# Main_4000_Model_REV1A.net
KiCad netlist of a schematic drawn in EAGLE
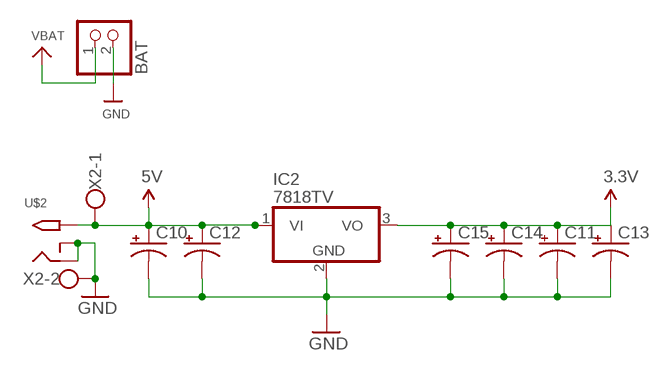
[diagram p0: schematic, sheet 1]
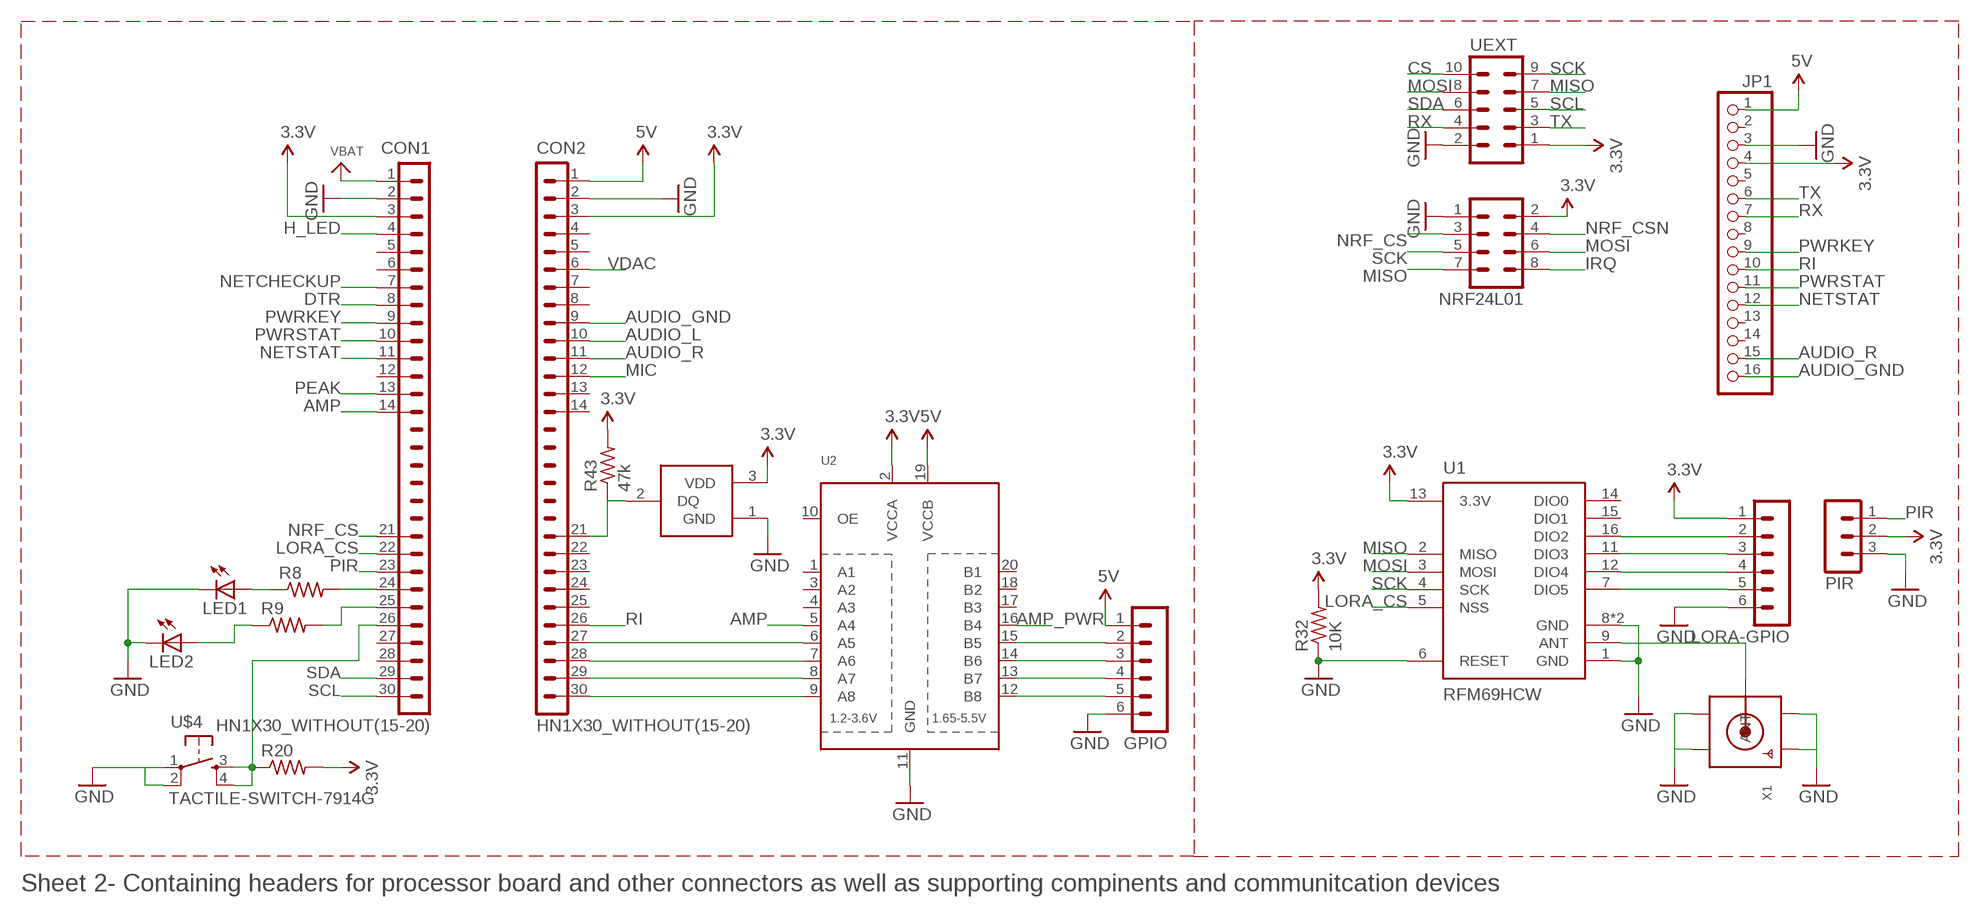
[diagram p1: schematic, sheet 2]
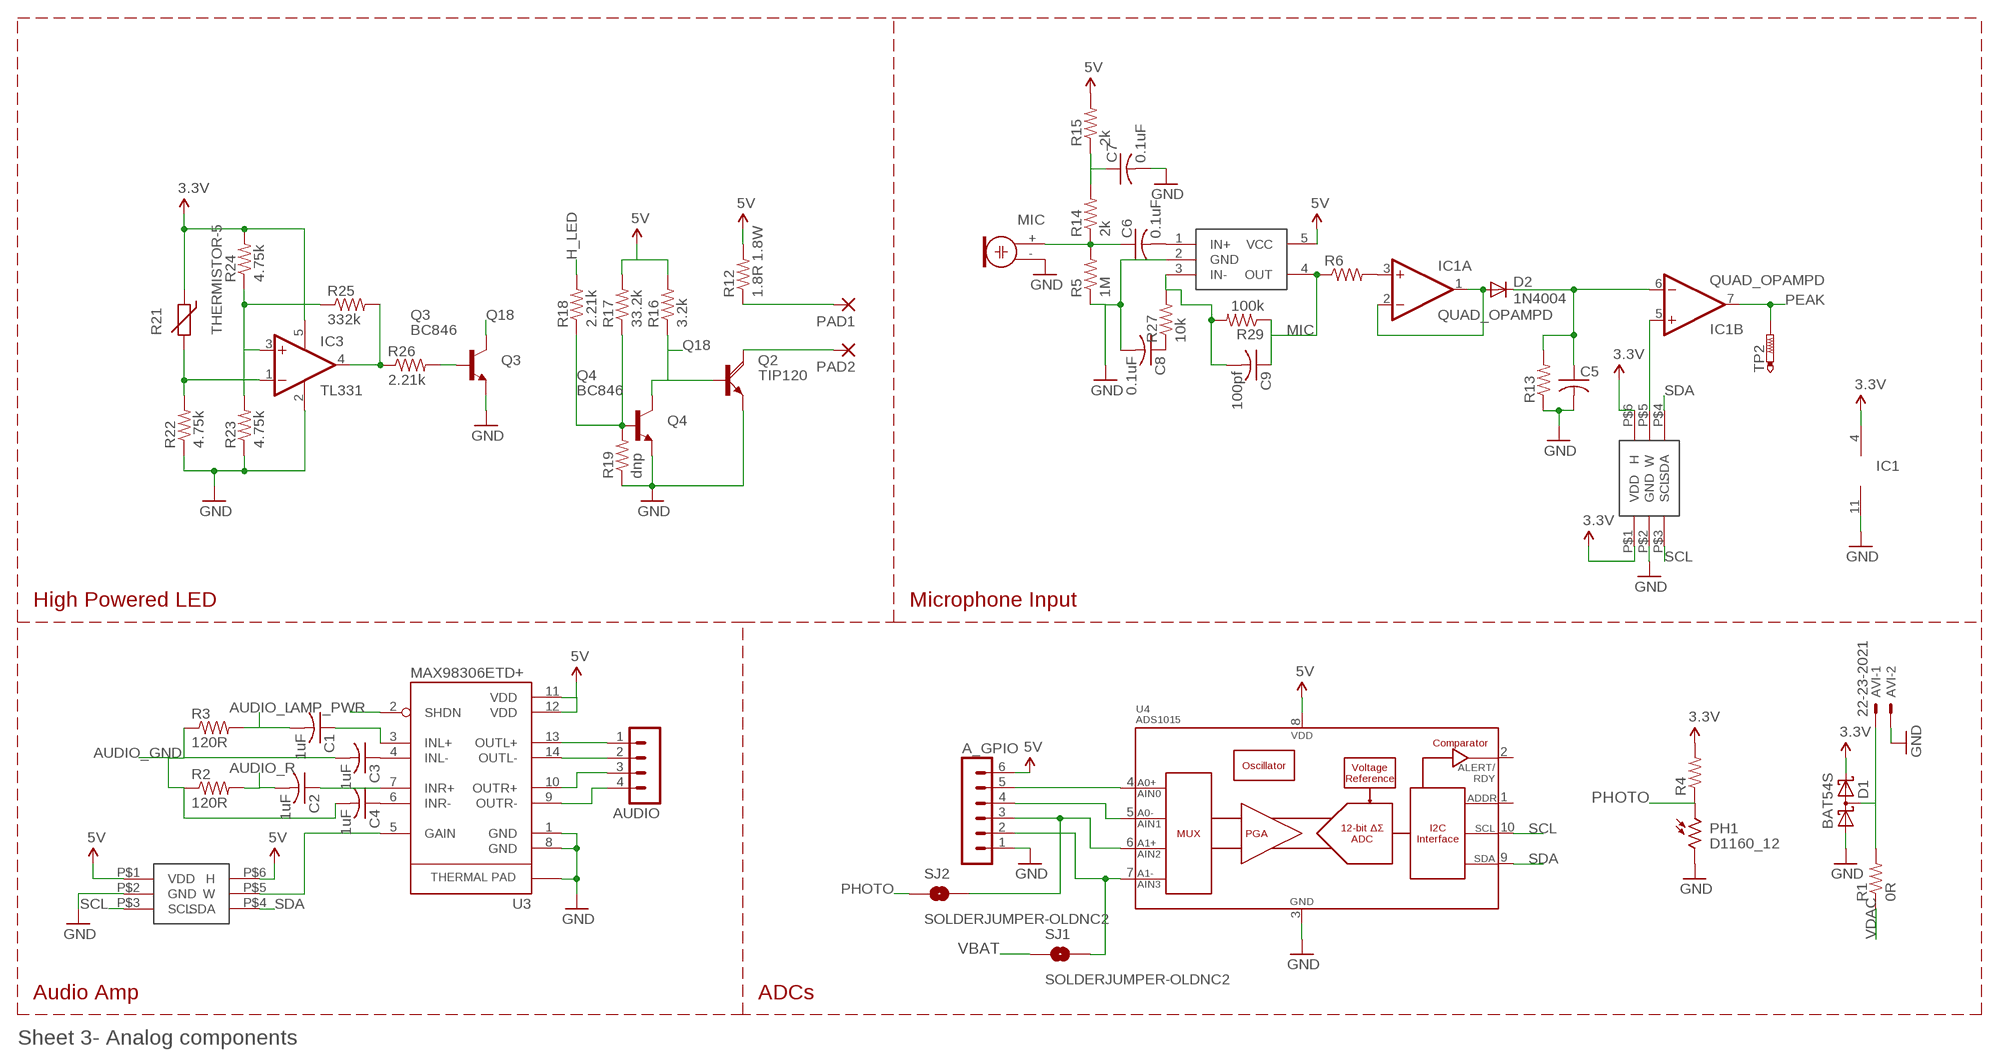
[diagram p2: schematic, sheet 3]
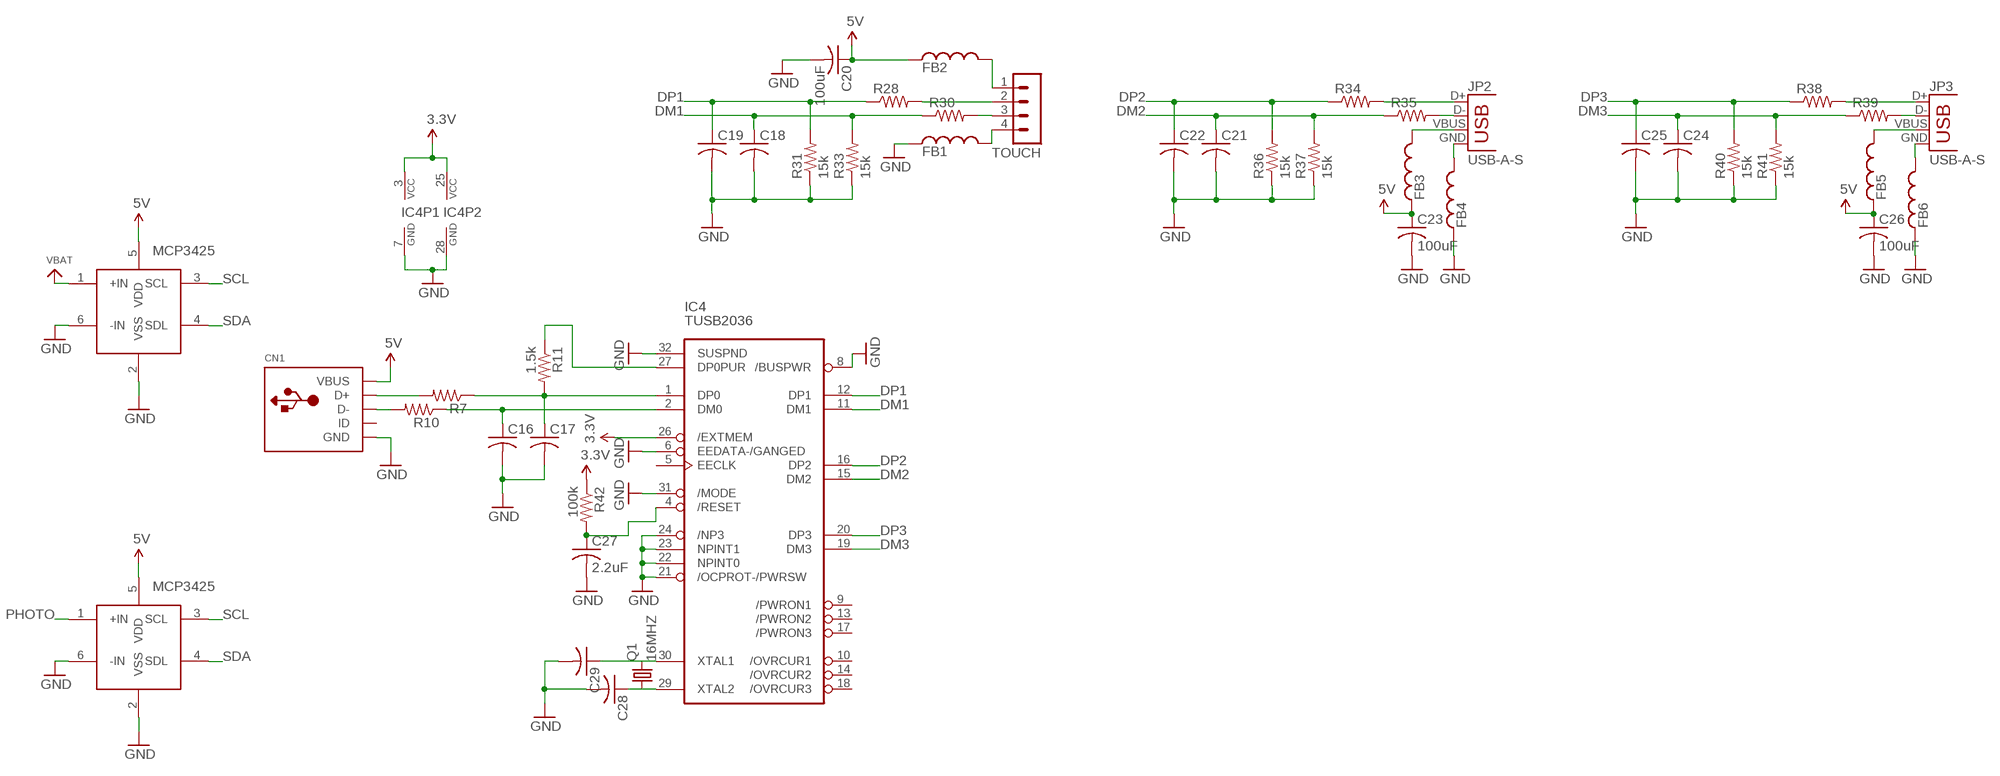
[diagram p3: schematic, sheet 4]

(export (version "E")
  (design (tool "Eeschema 10.0.6"))
  (components
    (comp (ref "CON1")
      (value "HN1X30_WITHOUT(15-20)")
      (footprint "eagle-import:HN1X30_WITHOUT(15-20)")
      (libsource (lib "eagle-import") (part "CON30_WITHOUT(15-20)"))
    )
    (comp (ref "CON2")
      (value "HN1X30_WITHOUT(15-20)")
      (footprint "eagle-import:HN1X30_WITHOUT(15-20)")
      (libsource (lib "eagle-import") (part "CON30_WITHOUT(15-20)"))
    )
    (comp (ref "GPIO")
      (value "MA06-1")
      (footprint "eagle-import:MA06-1")
      (libsource (lib "eagle-import") (part "MA06-1"))
    )
    (comp (ref "JP1")
      (value "PINHD-1X16")
      (footprint "eagle-import:1X16")
      (libsource (lib "eagle-import") (part "PINHD-1X16"))
    )
    (comp (ref "LED1")
      (value "LED5MM")
      (footprint "eagle-import:LED5MM")
      (libsource (lib "eagle-import") (part "LED5MM"))
    )
    (comp (ref "LED2")
      (value "LED5MM")
      (footprint "eagle-import:LED5MM")
      (libsource (lib "eagle-import") (part "LED5MM"))
    )
    (comp (ref "LORA-GPIO")
      (value "MA06-1")
      (footprint "eagle-import:MA06-1")
      (libsource (lib "eagle-import") (part "MA06-1"))
    )
    (comp (ref "NRF24L01")
      (value "MA04-2")
      (footprint "eagle-import:MA04-2")
      (libsource (lib "eagle-import") (part "MA04-2"))
    )
    (comp (ref "PIR")
      (value "MA03-1")
      (footprint "eagle-import:MA03-1")
      (libsource (lib "eagle-import") (part "MA03-1"))
    )
    (comp (ref "R8")
      (value "R-US_R0805")
      (footprint "eagle-import:R0805")
      (libsource (lib "eagle-import") (part "R-US_R0805"))
    )
    (comp (ref "R9")
      (value "R-US_R0805")
      (footprint "eagle-import:R0805")
      (libsource (lib "eagle-import") (part "R-US_R0805"))
    )
    (comp (ref "R20")
      (value "R-US_R0805")
      (footprint "eagle-import:R0805")
      (libsource (lib "eagle-import") (part "R-US_R0805"))
    )
    (comp (ref "R32")
      (value "10K")
      (footprint "eagle-import:R0805")
      (libsource (lib "eagle-import") (part "R-US_R0805"))
    )
    (comp (ref "R43")
      (value "47k")
      (footprint "eagle-import:R0805")
      (libsource (lib "eagle-import") (part "R-US_R0805"))
    )
    (comp (ref "U$4")
      (value "TACTILE-SWITCH-7914G")
      (footprint "eagle-import:7914G")
      (libsource (lib "eagle-import") (part "TACTILE-SWITCH-7914G"))
    )
    (comp (ref "U$11")
      (value "DS18B20Z")
      (footprint "eagle-import:TO92")
      (libsource (lib "eagle-import") (part "DS18B20Z"))
    )
    (comp (ref "U1")
      (value "RFM69HCW")
      (footprint "eagle-import:RFM69HCW-XXXS2")
      (libsource (lib "eagle-import") (part "RFM69HCW"))
    )
    (comp (ref "U2")
      (value "TXB0108PWR")
      (footprint "eagle-import:TSSOP20")
      (libsource (lib "eagle-import") (part "TXB0108PWR"))
    )
    (comp (ref "UEXT")
      (value "MA05-2")
      (footprint "eagle-import:MA05-2")
      (libsource (lib "eagle-import") (part "MA05-2"))
    )
    (comp (ref "X1")
      (value "SMACONNECTOR_EDGE")
      (footprint "eagle-import:SMA_EDGELAUNCH")
      (libsource (lib "eagle-import") (part "SMACONNECTOR_EDGE"))
    )
    (comp (ref "BAT")
      (value "JST_2PIN-SMT-RA")
      (footprint "eagle-import:JST-PH-2-SMT-RA")
      (libsource (lib "eagle-import") (part "JST_2PIN-SMT-RA"))
    )
    (comp (ref "C10")
      (value "CPOL-USE2.5-6")
      (footprint "eagle-import:E2,5-6")
      (libsource (lib "eagle-import") (part "CPOL-USE2.5-6"))
    )
    (comp (ref "C11")
      (value "CPOL-USE1.8-4")
      (footprint "eagle-import:E1,8-4")
      (libsource (lib "eagle-import") (part "CPOL-USE1.8-4"))
    )
    (comp (ref "C12")
      (value "CPOL-USE1.8-4")
      (footprint "eagle-import:E1,8-4")
      (libsource (lib "eagle-import") (part "CPOL-USE1.8-4"))
    )
    (comp (ref "C13")
      (value "CPOL-USE2.5-6")
      (footprint "eagle-import:E2,5-6")
      (libsource (lib "eagle-import") (part "CPOL-USE2.5-6"))
    )
    (comp (ref "C14")
      (value "CPOL-USE1.8-4")
      (footprint "eagle-import:E1,8-4")
      (libsource (lib "eagle-import") (part "CPOL-USE1.8-4"))
    )
    (comp (ref "C15")
      (value "CPOL-USE1.8-4")
      (footprint "eagle-import:E1,8-4")
      (libsource (lib "eagle-import") (part "CPOL-USE1.8-4"))
    )
    (comp (ref "IC2")
      (value "7818TV")
      (footprint "eagle-import:TO220V")
      (libsource (lib "eagle-import") (part "78TV18"))
    )
    (comp (ref "U$2")
      (value "2.1MMJACKTHM")
      (footprint "eagle-import:PJ-102A")
      (libsource (lib "eagle-import") (part "2.1MMJACKTHM"))
    )
    (comp (ref "X2")
      (value "W237-102")
      (footprint "eagle-import:W237-102")
      (fields (field (name "MPN") "237-102"))
      (libsource (lib "eagle-import") (part "W237-102"))
    )
    (comp (ref "C16")
      (value "C-USC0805")
      (footprint "eagle-import:C0805")
      (libsource (lib "eagle-import") (part "C-USC0805"))
    )
    (comp (ref "C17")
      (value "C-USC0805")
      (footprint "eagle-import:C0805")
      (libsource (lib "eagle-import") (part "C-USC0805"))
    )
    (comp (ref "C18")
      (value "C-USC0805")
      (footprint "eagle-import:C0805")
      (libsource (lib "eagle-import") (part "C-USC0805"))
    )
    (comp (ref "C19")
      (value "C-USC0805")
      (footprint "eagle-import:C0805")
      (libsource (lib "eagle-import") (part "C-USC0805"))
    )
    (comp (ref "C20")
      (value "100uF")
      (footprint "eagle-import:C0805")
      (libsource (lib "eagle-import") (part "C-USC0805"))
    )
    (comp (ref "C21")
      (value "C-USC0805")
      (footprint "eagle-import:C0805")
      (libsource (lib "eagle-import") (part "C-USC0805"))
    )
    (comp (ref "C22")
      (value "C-USC0805")
      (footprint "eagle-import:C0805")
      (libsource (lib "eagle-import") (part "C-USC0805"))
    )
    (comp (ref "C23")
      (value "100uF")
      (footprint "eagle-import:C0805")
      (libsource (lib "eagle-import") (part "C-USC0805"))
    )
    (comp (ref "C24")
      (value "C-USC0805")
      (footprint "eagle-import:C0805")
      (libsource (lib "eagle-import") (part "C-USC0805"))
    )
    (comp (ref "C25")
      (value "C-USC0805")
      (footprint "eagle-import:C0805")
      (libsource (lib "eagle-import") (part "C-USC0805"))
    )
    (comp (ref "C26")
      (value "100uF")
      (footprint "eagle-import:C0805")
      (libsource (lib "eagle-import") (part "C-USC0805"))
    )
    (comp (ref "C27")
      (value "2.2uF")
      (footprint "eagle-import:C0805")
      (libsource (lib "eagle-import") (part "C-USC0805"))
    )
    (comp (ref "C28")
      (value "C-USC0805")
      (footprint "eagle-import:C0805")
      (libsource (lib "eagle-import") (part "C-USC0805"))
    )
    (comp (ref "C29")
      (value "C-USC0805")
      (footprint "eagle-import:C0805")
      (libsource (lib "eagle-import") (part "C-USC0805"))
    )
    (comp (ref "CN1")
      (value "USBMOLEX")
      (footprint "eagle-import:USB-MINIB-THM-MOLEX")
      (libsource (lib "eagle-import") (part "USBMOLEX"))
    )
    (comp (ref "FB1")
      (value "FB1206")
      (footprint "eagle-import:FB1206")
      (libsource (lib "eagle-import") (part "FB1206"))
    )
    (comp (ref "FB2")
      (value "FB1206")
      (footprint "eagle-import:FB1206")
      (libsource (lib "eagle-import") (part "FB1206"))
    )
    (comp (ref "FB3")
      (value "FB1206")
      (footprint "eagle-import:FB1206")
      (libsource (lib "eagle-import") (part "FB1206"))
    )
    (comp (ref "FB4")
      (value "FB1206")
      (footprint "eagle-import:FB1206")
      (libsource (lib "eagle-import") (part "FB1206"))
    )
    (comp (ref "FB5")
      (value "FB1206")
      (footprint "eagle-import:FB1206")
      (libsource (lib "eagle-import") (part "FB1206"))
    )
    (comp (ref "FB6")
      (value "FB1206")
      (footprint "eagle-import:FB1206")
      (libsource (lib "eagle-import") (part "FB1206"))
    )
    (comp (ref "IC4")
      (value "TUSB2036")
      (footprint "eagle-import:LQFP32")
      (libsource (lib "eagle-import") (part "TUSB2036"))
    )
    (comp (ref "JP2")
      (value "USB-A-S")
      (footprint "eagle-import:USB-A-S")
      (libsource (lib "eagle-import") (part "USB-A-S"))
    )
    (comp (ref "JP3")
      (value "USB-A-S")
      (footprint "eagle-import:USB-A-S")
      (libsource (lib "eagle-import") (part "USB-A-S"))
    )
    (comp (ref "Q1")
      (value "16MHZ")
      (footprint "eagle-import:HC49UP")
      (libsource (lib "eagle-import") (part "CRYSTALHC49UP"))
    )
    (comp (ref "R7")
      (value "R-US_R0805")
      (footprint "eagle-import:R0805")
      (libsource (lib "eagle-import") (part "R-US_R0805"))
    )
    (comp (ref "R10")
      (value "R-US_R0805")
      (footprint "eagle-import:R0805")
      (libsource (lib "eagle-import") (part "R-US_R0805"))
    )
    (comp (ref "R11")
      (value "1.5k")
      (footprint "eagle-import:R0805")
      (libsource (lib "eagle-import") (part "R-US_R0805"))
    )
    (comp (ref "R28")
      (value "R-US_R0805")
      (footprint "eagle-import:R0805")
      (libsource (lib "eagle-import") (part "R-US_R0805"))
    )
    (comp (ref "R30")
      (value "R-US_R0805")
      (footprint "eagle-import:R0805")
      (libsource (lib "eagle-import") (part "R-US_R0805"))
    )
    (comp (ref "R31")
      (value "15k")
      (footprint "eagle-import:R0805")
      (libsource (lib "eagle-import") (part "R-US_R0805"))
    )
    (comp (ref "R33")
      (value "15k")
      (footprint "eagle-import:R0805")
      (libsource (lib "eagle-import") (part "R-US_R0805"))
    )
    (comp (ref "R34")
      (value "R-US_R0805")
      (footprint "eagle-import:R0805")
      (libsource (lib "eagle-import") (part "R-US_R0805"))
    )
    (comp (ref "R35")
      (value "R-US_R0805")
      (footprint "eagle-import:R0805")
      (libsource (lib "eagle-import") (part "R-US_R0805"))
    )
    (comp (ref "R36")
      (value "15k")
      (footprint "eagle-import:R0805")
      (libsource (lib "eagle-import") (part "R-US_R0805"))
    )
    (comp (ref "R37")
      (value "15k")
      (footprint "eagle-import:R0805")
      (libsource (lib "eagle-import") (part "R-US_R0805"))
    )
    (comp (ref "R38")
      (value "R-US_R0805")
      (footprint "eagle-import:R0805")
      (libsource (lib "eagle-import") (part "R-US_R0805"))
    )
    (comp (ref "R39")
      (value "R-US_R0805")
      (footprint "eagle-import:R0805")
      (libsource (lib "eagle-import") (part "R-US_R0805"))
    )
    (comp (ref "R40")
      (value "15k")
      (footprint "eagle-import:R0805")
      (libsource (lib "eagle-import") (part "R-US_R0805"))
    )
    (comp (ref "R41")
      (value "15k")
      (footprint "eagle-import:R0805")
      (libsource (lib "eagle-import") (part "R-US_R0805"))
    )
    (comp (ref "R42")
      (value "100k")
      (footprint "eagle-import:R0805")
      (libsource (lib "eagle-import") (part "R-US_R0805"))
    )
    (comp (ref "TOUCH")
      (value "MA04-1")
      (footprint "eagle-import:MA04-1")
      (libsource (lib "eagle-import") (part "MA04-1"))
    )
    (comp (ref "U$6")
      (value "MCP3425SOT")
      (footprint "eagle-import:SOT23-6")
      (libsource (lib "eagle-import") (part "MCP3425SOT"))
    )
    (comp (ref "U$8")
      (value "MCP3425SOT")
      (footprint "eagle-import:SOT23-6")
      (libsource (lib "eagle-import") (part "MCP3425SOT"))
    )
    (comp (ref "AUDIO")
      (value "MA04-1")
      (footprint "eagle-import:MA04-1")
      (libsource (lib "eagle-import") (part "MA04-1"))
    )
    (comp (ref "AVI")
      (value "22-23-2021")
      (footprint "eagle-import:22-23-2021")
      (fields (field (name "MF") "MOLEX"))
      (libsource (lib "eagle-import") (part "22-23-2021"))
    )
    (comp (ref "A_GPIO")
      (value "MA06-1")
      (footprint "eagle-import:MA06-1")
      (libsource (lib "eagle-import") (part "MA06-1"))
    )
    (comp (ref "C1")
      (value "1uF")
      (footprint "eagle-import:C0805")
      (libsource (lib "eagle-import") (part "C-USC0805"))
    )
    (comp (ref "C2")
      (value "1uF")
      (footprint "eagle-import:C0805")
      (libsource (lib "eagle-import") (part "C-USC0805"))
    )
    (comp (ref "C3")
      (value "1uF")
      (footprint "eagle-import:C0805")
      (libsource (lib "eagle-import") (part "C-USC0805"))
    )
    (comp (ref "C4")
      (value "1uF")
      (footprint "eagle-import:C0805")
      (libsource (lib "eagle-import") (part "C-USC0805"))
    )
    (comp (ref "C5")
      (value "C-USC0805K")
      (footprint "eagle-import:C0805K")
      (libsource (lib "eagle-import") (part "C-USC0805K"))
    )
    (comp (ref "C6")
      (value "0.1uF")
      (footprint "eagle-import:C0805")
      (libsource (lib "eagle-import") (part "C-USC0805"))
    )
    (comp (ref "C7")
      (value "0.1uF")
      (footprint "eagle-import:C0805")
      (libsource (lib "eagle-import") (part "C-USC0805"))
    )
    (comp (ref "C8")
      (value "0.1uF")
      (footprint "eagle-import:C0805")
      (libsource (lib "eagle-import") (part "C-USC0805"))
    )
    (comp (ref "C9")
      (value "100pf")
      (footprint "eagle-import:C0805")
      (libsource (lib "eagle-import") (part "C-USC0805"))
    )
    (comp (ref "D1")
      (value "BAT54S")
      (footprint "eagle-import:SOT23")
      (libsource (lib "eagle-import") (part "BAT54S"))
    )
    (comp (ref "D2")
      (value "1N4004")
      (footprint "eagle-import:DO41-10")
      (libsource (lib "eagle-import") (part "1N4004"))
    )
    (comp (ref "IC1")
      (value "QUAD_OPAMPD")
      (footprint "eagle-import:SO14")
      (libsource (lib "eagle-import") (part "QUAD_OPAMPD"))
    )
    (comp (ref "IC3")
      (value "TL331")
      (footprint "eagle-import:DBV-R-PDSO-G5")
      (libsource (lib "eagle-import") (part "TL331"))
    )
    (comp (ref "MIC")
      (value "ELECTRET")
      (footprint "eagle-import:9.7ELECTRET")
      (libsource (lib "eagle-import") (part "ELECTRET"))
    )
    (comp (ref "PAD1")
      (value "3,81/1,4")
      (footprint "eagle-import:3,81_1,4")
      (libsource (lib "eagle-import") (part "3,81/1,4"))
    )
    (comp (ref "PAD2")
      (value "3,81/1,4")
      (footprint "eagle-import:3,81_1,4")
      (libsource (lib "eagle-import") (part "3,81/1,4"))
    )
    (comp (ref "PH1")
      (value "D1160_12")
      (footprint "eagle-import:D11XX")
      (libsource (lib "eagle-import") (part "D1160_12"))
    )
    (comp (ref "Q2")
      (value "TIP120")
      (footprint "eagle-import:TO220AH")
      (libsource (lib "eagle-import") (part "TIP120"))
    )
    (comp (ref "Q3")
      (value "BC846")
      (footprint "eagle-import:SOT23")
      (libsource (lib "eagle-import") (part "BC846"))
    )
    (comp (ref "Q4")
      (value "BC846")
      (footprint "eagle-import:SOT23")
      (libsource (lib "eagle-import") (part "BC846"))
    )
    (comp (ref "R1")
      (value "0R")
      (footprint "eagle-import:R0805")
      (libsource (lib "eagle-import") (part "R-US_R0805"))
    )
    (comp (ref "R2")
      (value "120R")
      (footprint "eagle-import:R0805")
      (libsource (lib "eagle-import") (part "R-US_R0805"))
    )
    (comp (ref "R3")
      (value "120R")
      (footprint "eagle-import:R0805")
      (libsource (lib "eagle-import") (part "R-US_R0805"))
    )
    (comp (ref "R4")
      (value "R-US_R0805")
      (footprint "eagle-import:R0805")
      (libsource (lib "eagle-import") (part "R-US_R0805"))
    )
    (comp (ref "R5")
      (value "1M")
      (footprint "eagle-import:R0805")
      (libsource (lib "eagle-import") (part "R-US_R0805"))
    )
    (comp (ref "R6")
      (value "R-US_R0805")
      (footprint "eagle-import:R0805")
      (libsource (lib "eagle-import") (part "R-US_R0805"))
    )
    (comp (ref "R12")
      (value "1.8R 1.8W")
      (footprint "eagle-import:VMTB60")
      (libsource (lib "eagle-import") (part "R-US_VMTB60"))
    )
    (comp (ref "R13")
      (value "R-US_R0805")
      (footprint "eagle-import:R0805")
      (libsource (lib "eagle-import") (part "R-US_R0805"))
    )
    (comp (ref "R14")
      (value "2k")
      (footprint "eagle-import:R0805")
      (libsource (lib "eagle-import") (part "R-US_R0805"))
    )
    (comp (ref "R15")
      (value "2k")
      (footprint "eagle-import:R0805")
      (libsource (lib "eagle-import") (part "R-US_R0805"))
    )
    (comp (ref "R16")
      (value "3.2k")
      (footprint "eagle-import:R0805")
      (libsource (lib "eagle-import") (part "R-US_R0805"))
    )
    (comp (ref "R17")
      (value "33.2k")
      (footprint "eagle-import:R0805")
      (libsource (lib "eagle-import") (part "R-US_R0805"))
    )
    (comp (ref "R18")
      (value "2.21k")
      (footprint "eagle-import:R0805")
      (libsource (lib "eagle-import") (part "R-US_R0805"))
    )
    (comp (ref "R19")
      (value "dnp")
      (footprint "eagle-import:R0805")
      (libsource (lib "eagle-import") (part "R-US_R0805"))
    )
    (comp (ref "R21")
      (value "THERMISTOR-5")
      (footprint "eagle-import:R-5")
      (libsource (lib "eagle-import") (part "THERMISTOR-5"))
    )
    (comp (ref "R22")
      (value "4.75k")
      (footprint "eagle-import:R0805")
      (libsource (lib "eagle-import") (part "R-US_R0805"))
    )
    (comp (ref "R23")
      (value "4.75k")
      (footprint "eagle-import:R0805")
      (libsource (lib "eagle-import") (part "R-US_R0805"))
    )
    (comp (ref "R24")
      (value "4.75k")
      (footprint "eagle-import:R0805")
      (libsource (lib "eagle-import") (part "R-US_R0805"))
    )
    (comp (ref "R25")
      (value "332k")
      (footprint "eagle-import:R0805")
      (libsource (lib "eagle-import") (part "R-US_R0805"))
    )
    (comp (ref "R26")
      (value "2.21k")
      (footprint "eagle-import:R0805")
      (libsource (lib "eagle-import") (part "R-US_R0805"))
    )
    (comp (ref "R27")
      (value "10k")
      (footprint "eagle-import:R0805")
      (libsource (lib "eagle-import") (part "R-US_R0805"))
    )
    (comp (ref "R29")
      (value "100k")
      (footprint "eagle-import:R0805")
      (libsource (lib "eagle-import") (part "R-US_R0805"))
    )
    (comp (ref "SJ1")
      (value "SOLDERJUMPER-OLDNC2")
      (footprint "eagle-import:SJ_2S-NOTRACE")
      (libsource (lib "eagle-import") (part "SOLDERJUMPER-OLDNC2"))
    )
    (comp (ref "SJ2")
      (value "SOLDERJUMPER-OLDNC2")
      (footprint "eagle-import:SJ_2S-NOTRACE")
      (libsource (lib "eagle-import") (part "SOLDERJUMPER-OLDNC2"))
    )
    (comp (ref "TP2")
      (value "PTR1PAD1-13")
      (footprint "eagle-import:P1-13")
      (libsource (lib "eagle-import") (part "PTR1PAD1-13"))
    )
    (comp (ref "U$1")
      (value "TPL0401A/B")
      (footprint "eagle-import:SC-70")
      (libsource (lib "eagle-import") (part "TPL0401A/B"))
    )
    (comp (ref "U$3")
      (value "MAX4466")
      (footprint "eagle-import:SOT23-5L")
      (libsource (lib "eagle-import") (part "MAX4466"))
    )
    (comp (ref "U$5")
      (value "TPL0401A/B")
      (footprint "eagle-import:SC-70")
      (libsource (lib "eagle-import") (part "TPL0401A/B"))
    )
    (comp (ref "U3")
      (value "MAX98306ETD+")
      (footprint "eagle-import:14-TDFN")
      (libsource (lib "eagle-import") (part "MAX98306ETD+"))
    )
    (comp (ref "U4")
      (value "ADS1015")
      (footprint "eagle-import:MSOP10")
      (libsource (lib "eagle-import") (part "ADS1015"))
    )
  )
  (nets
    (net (code "1") (name "3.3V") (class "Default")
      (node (ref "C11") (pin "+") (pinfunction "+_+") (pintype "passive"))
      (node (ref "C13") (pin "+") (pinfunction "+_+") (pintype "passive"))
      (node (ref "C14") (pin "+") (pinfunction "+_+") (pintype "passive"))
      (node (ref "C15") (pin "+") (pinfunction "+_+") (pintype "passive"))
      (node (ref "CON1") (pin "3") (pinfunction "3_3") (pintype "passive"))
      (node (ref "CON2") (pin "3") (pinfunction "3_3") (pintype "passive"))
      (node (ref "D1") (pin "2") (pinfunction "C2_2") (pintype "passive"))
      (node (ref "IC1") (pin "4") (pinfunction "V+_4") (pintype "power_in"))
      (node (ref "IC2") (pin "3") (pinfunction "VO_3") (pintype "passive"))
      (node (ref "IC3") (pin "5") (pinfunction "V+_5") (pintype "power_in"))
      (node (ref "IC4") (pin "25") (pinfunction "VCC_25") (pintype "power_in"))
      (node (ref "IC4") (pin "26") (pinfunction "/EXTMEM_26") (pintype "input"))
      (node (ref "IC4") (pin "3") (pinfunction "VCC_3") (pintype "power_in"))
      (node (ref "JP1") (pin "4") (pinfunction "4_4") (pintype "passive"))
      (node (ref "LORA-GPIO") (pin "1") (pinfunction "1_1") (pintype "passive"))
      (node (ref "NRF24L01") (pin "2") (pinfunction "2_2") (pintype "passive"))
      (node (ref "PIR") (pin "2") (pinfunction "2_2") (pintype "passive"))
      (node (ref "R20") (pin "2") (pinfunction "2_2") (pintype "passive"))
      (node (ref "R21") (pin "1") (pinfunction "1_1") (pintype "passive"))
      (node (ref "R24") (pin "2") (pinfunction "2_2") (pintype "passive"))
      (node (ref "R32") (pin "2") (pinfunction "2_2") (pintype "passive"))
      (node (ref "R4") (pin "2") (pinfunction "2_2") (pintype "passive"))
      (node (ref "R42") (pin "1") (pinfunction "1_1") (pintype "passive"))
      (node (ref "R43") (pin "2") (pinfunction "2_2") (pintype "passive"))
      (node (ref "U$11") (pin "3") (pinfunction "VDD_3") (pintype "bidirectional"))
      (node (ref "U$5") (pin "P$1") (pinfunction "VDD_P$1") (pintype "bidirectional"))
      (node (ref "U$5") (pin "P$6") (pinfunction "H_P$6") (pintype "bidirectional"))
      (node (ref "U1") (pin "13") (pinfunction "3.3V_13") (pintype "power_in"))
      (node (ref "U2") (pin "2") (pinfunction "VCCA_2") (pintype "bidirectional"))
      (node (ref "UEXT") (pin "1") (pinfunction "1_1") (pintype "passive"))
    )
    (net (code "2") (name "5V") (class "Default")
      (node (ref "A_GPIO") (pin "6") (pinfunction "6_6") (pintype "passive"))
      (node (ref "C10") (pin "+") (pinfunction "+_+") (pintype "passive"))
      (node (ref "C12") (pin "+") (pinfunction "+_+") (pintype "passive"))
      (node (ref "C20") (pin "1") (pinfunction "1_1") (pintype "passive"))
      (node (ref "C23") (pin "1") (pinfunction "1_1") (pintype "passive"))
      (node (ref "C26") (pin "1") (pinfunction "1_1") (pintype "passive"))
      (node (ref "CN1") (pin "VBUS") (pinfunction "VBUS_VBUS") (pintype "power_in"))
      (node (ref "CON2") (pin "1") (pinfunction "1_1") (pintype "passive"))
      (node (ref "FB2") (pin "1") (pinfunction "1_1") (pintype "passive"))
      (node (ref "FB3") (pin "1") (pinfunction "1_1") (pintype "passive"))
      (node (ref "FB5") (pin "1") (pinfunction "1_1") (pintype "passive"))
      (node (ref "GPIO") (pin "1") (pinfunction "1_1") (pintype "passive"))
      (node (ref "IC2") (pin "1") (pinfunction "VI_1") (pintype "input"))
      (node (ref "JP1") (pin "1") (pinfunction "1_1") (pintype "passive"))
      (node (ref "R12") (pin "2") (pinfunction "2_2") (pintype "passive"))
      (node (ref "R15") (pin "2") (pinfunction "2_2") (pintype "passive"))
      (node (ref "R16") (pin "2") (pinfunction "2_2") (pintype "passive"))
      (node (ref "R17") (pin "2") (pinfunction "2_2") (pintype "passive"))
      (node (ref "U$1") (pin "P$1") (pinfunction "VDD_P$1") (pintype "bidirectional"))
      (node (ref "U$1") (pin "P$6") (pinfunction "H_P$6") (pintype "bidirectional"))
      (node (ref "U$2") (pin "TIP") (pinfunction "TIP_TIP") (pintype "bidirectional"))
      (node (ref "U$3") (pin "5") (pinfunction "VCC_5") (pintype "bidirectional"))
      (node (ref "U$6") (pin "5") (pinfunction "VDD_5") (pintype "bidirectional"))
      (node (ref "U$8") (pin "5") (pinfunction "VDD_5") (pintype "bidirectional"))
      (node (ref "U2") (pin "19") (pinfunction "VCCB_19") (pintype "bidirectional"))
      (node (ref "U3") (pin "11") (pinfunction "VDD_11") (pintype "power_in"))
      (node (ref "U3") (pin "12") (pinfunction "VDD_12") (pintype "power_in"))
      (node (ref "U4") (pin "8") (pinfunction "VDD_8") (pintype "bidirectional"))
      (node (ref "X2") (pin "1") (pinfunction "KL_1") (pintype "passive"))
    )
    (net (code "3") (name "AMP") (class "Default")
      (node (ref "CON1") (pin "14") (pinfunction "14_14") (pintype "passive"))
      (node (ref "U2") (pin "5") (pinfunction "A4_5") (pintype "bidirectional"))
    )
    (net (code "4") (name "AMP_PWR") (class "Default")
      (node (ref "U2") (pin "16") (pinfunction "B4_16") (pintype "bidirectional"))
      (node (ref "U3") (pin "2") (pinfunction "SHDN_2") (pintype "input"))
    )
    (net (code "5") (name "AUDIO_GND") (class "Default")
      (node (ref "C3") (pin "2") (pinfunction "2_2") (pintype "passive"))
      (node (ref "C4") (pin "2") (pinfunction "2_2") (pintype "passive"))
      (node (ref "CON2") (pin "9") (pinfunction "9_9") (pintype "passive"))
      (node (ref "JP1") (pin "16") (pinfunction "16_16") (pintype "passive"))
      (node (ref "R2") (pin "1") (pinfunction "1_1") (pintype "passive"))
      (node (ref "R3") (pin "1") (pinfunction "1_1") (pintype "passive"))
    )
    (net (code "6") (name "AUDIO_L") (class "Default")
      (node (ref "C1") (pin "2") (pinfunction "2_2") (pintype "passive"))
      (node (ref "CON2") (pin "10") (pinfunction "10_10") (pintype "passive"))
      (node (ref "R3") (pin "2") (pinfunction "2_2") (pintype "passive"))
    )
    (net (code "7") (name "AUDIO_R") (class "Default")
      (node (ref "C2") (pin "2") (pinfunction "2_2") (pintype "passive"))
      (node (ref "CON2") (pin "11") (pinfunction "11_11") (pintype "passive"))
      (node (ref "JP1") (pin "15") (pinfunction "15_15") (pintype "passive"))
      (node (ref "R2") (pin "2") (pinfunction "2_2") (pintype "passive"))
    )
    (net (code "8") (name "CS") (class "Default")
      (node (ref "UEXT") (pin "10") (pinfunction "10_10") (pintype "passive"))
    )
    (net (code "9") (name "DM1") (class "Default")
      (node (ref "C18") (pin "1") (pinfunction "1_1") (pintype "passive"))
      (node (ref "IC4") (pin "11") (pinfunction "DM1_11") (pintype "bidirectional"))
      (node (ref "R30") (pin "1") (pinfunction "1_1") (pintype "passive"))
      (node (ref "R33") (pin "2") (pinfunction "2_2") (pintype "passive"))
    )
    (net (code "10") (name "DM2") (class "Default")
      (node (ref "C21") (pin "1") (pinfunction "1_1") (pintype "passive"))
      (node (ref "IC4") (pin "15") (pinfunction "DM2_15") (pintype "bidirectional"))
      (node (ref "R35") (pin "1") (pinfunction "1_1") (pintype "passive"))
      (node (ref "R37") (pin "2") (pinfunction "2_2") (pintype "passive"))
    )
    (net (code "11") (name "DM3") (class "Default")
      (node (ref "C24") (pin "1") (pinfunction "1_1") (pintype "passive"))
      (node (ref "IC4") (pin "19") (pinfunction "DM3_19") (pintype "bidirectional"))
      (node (ref "R39") (pin "1") (pinfunction "1_1") (pintype "passive"))
      (node (ref "R41") (pin "2") (pinfunction "2_2") (pintype "passive"))
    )
    (net (code "12") (name "DP1") (class "Default")
      (node (ref "C19") (pin "1") (pinfunction "1_1") (pintype "passive"))
      (node (ref "IC4") (pin "12") (pinfunction "DP1_12") (pintype "bidirectional"))
      (node (ref "R28") (pin "1") (pinfunction "1_1") (pintype "passive"))
      (node (ref "R31") (pin "2") (pinfunction "2_2") (pintype "passive"))
    )
    (net (code "13") (name "DP2") (class "Default")
      (node (ref "C22") (pin "1") (pinfunction "1_1") (pintype "passive"))
      (node (ref "IC4") (pin "16") (pinfunction "DP2_16") (pintype "bidirectional"))
      (node (ref "R34") (pin "1") (pinfunction "1_1") (pintype "passive"))
      (node (ref "R36") (pin "2") (pinfunction "2_2") (pintype "passive"))
    )
    (net (code "14") (name "DP3") (class "Default")
      (node (ref "C25") (pin "1") (pinfunction "1_1") (pintype "passive"))
      (node (ref "IC4") (pin "20") (pinfunction "DP3_20") (pintype "bidirectional"))
      (node (ref "R38") (pin "1") (pinfunction "1_1") (pintype "passive"))
      (node (ref "R40") (pin "2") (pinfunction "2_2") (pintype "passive"))
    )
    (net (code "15") (name "DTR") (class "Default")
      (node (ref "CON1") (pin "8") (pinfunction "8_8") (pintype "passive"))
    )
    (net (code "16") (name "GND") (class "Default")
      (node (ref "AVI") (pin "2") (pinfunction "S_2") (pintype "passive"))
      (node (ref "A_GPIO") (pin "1") (pinfunction "1_1") (pintype "passive"))
      (node (ref "BAT") (pin "2") (pinfunction "1_2") (pintype "passive"))
      (node (ref "C10") (pin "-") (pinfunction "-_-") (pintype "passive"))
      (node (ref "C11") (pin "-") (pinfunction "-_-") (pintype "passive"))
      (node (ref "C12") (pin "-") (pinfunction "-_-") (pintype "passive"))
      (node (ref "C13") (pin "-") (pinfunction "-_-") (pintype "passive"))
      (node (ref "C14") (pin "-") (pinfunction "-_-") (pintype "passive"))
      (node (ref "C15") (pin "-") (pinfunction "-_-") (pintype "passive"))
      (node (ref "C16") (pin "2") (pinfunction "2_2") (pintype "passive"))
      (node (ref "C17") (pin "2") (pinfunction "2_2") (pintype "passive"))
      (node (ref "C18") (pin "2") (pinfunction "2_2") (pintype "passive"))
      (node (ref "C19") (pin "2") (pinfunction "2_2") (pintype "passive"))
      (node (ref "C20") (pin "2") (pinfunction "2_2") (pintype "passive"))
      (node (ref "C21") (pin "2") (pinfunction "2_2") (pintype "passive"))
      (node (ref "C22") (pin "2") (pinfunction "2_2") (pintype "passive"))
      (node (ref "C23") (pin "2") (pinfunction "2_2") (pintype "passive"))
      (node (ref "C24") (pin "2") (pinfunction "2_2") (pintype "passive"))
      (node (ref "C25") (pin "2") (pinfunction "2_2") (pintype "passive"))
      (node (ref "C26") (pin "2") (pinfunction "2_2") (pintype "passive"))
      (node (ref "C27") (pin "2") (pinfunction "2_2") (pintype "passive"))
      (node (ref "C28") (pin "2") (pinfunction "2_2") (pintype "passive"))
      (node (ref "C29") (pin "2") (pinfunction "2_2") (pintype "passive"))
      (node (ref "C5") (pin "2") (pinfunction "2_2") (pintype "passive"))
      (node (ref "C7") (pin "2") (pinfunction "2_2") (pintype "passive"))
      (node (ref "C8") (pin "2") (pinfunction "2_2") (pintype "passive"))
      (node (ref "CN1") (pin "GND") (pinfunction "GND_GND") (pintype "power_in"))
      (node (ref "CON1") (pin "2") (pinfunction "2_2") (pintype "passive"))
      (node (ref "CON2") (pin "2") (pinfunction "2_2") (pintype "passive"))
      (node (ref "D1") (pin "1") (pinfunction "A1_1") (pintype "passive"))
      (node (ref "FB1") (pin "1") (pinfunction "1_1") (pintype "passive"))
      (node (ref "FB4") (pin "1") (pinfunction "1_1") (pintype "passive"))
      (node (ref "FB6") (pin "1") (pinfunction "1_1") (pintype "passive"))
      (node (ref "GPIO") (pin "6") (pinfunction "6_6") (pintype "passive"))
      (node (ref "IC1") (pin "11") (pinfunction "V-_11") (pintype "power_in"))
      (node (ref "IC2") (pin "2") (pinfunction "GND_2") (pintype "passive"))
      (node (ref "IC3") (pin "2") (pinfunction "GND_2") (pintype "power_in"))
      (node (ref "IC4") (pin "21") (pinfunction "/OCPROT-/PWRSW_21") (pintype "input"))
      (node (ref "IC4") (pin "22") (pinfunction "NPINT0_22") (pintype "input"))
      (node (ref "IC4") (pin "23") (pinfunction "NPINT1_23") (pintype "input"))
      (node (ref "IC4") (pin "24") (pinfunction "/NP3_24") (pintype "input"))
      (node (ref "IC4") (pin "28") (pinfunction "GND_28") (pintype "power_in"))
      (node (ref "IC4") (pin "31") (pinfunction "/MODE_31") (pintype "input"))
      (node (ref "IC4") (pin "32") (pinfunction "SUSPND_32") (pintype "output"))
      (node (ref "IC4") (pin "6") (pinfunction "EEDATA-/GANGED_6") (pintype "bidirectional"))
      (node (ref "IC4") (pin "7") (pinfunction "GND_7") (pintype "power_in"))
      (node (ref "IC4") (pin "8") (pinfunction "/BUSPWR_8") (pintype "input"))
      (node (ref "JP1") (pin "3") (pinfunction "3_3") (pintype "passive"))
      (node (ref "LED1") (pin "K") (pinfunction "C_K") (pintype "passive"))
      (node (ref "LED2") (pin "K") (pinfunction "C_K") (pintype "passive"))
      (node (ref "LORA-GPIO") (pin "6") (pinfunction "6_6") (pintype "passive"))
      (node (ref "MIC") (pin "-") (pinfunction "1_-") (pintype "passive"))
      (node (ref "NRF24L01") (pin "1") (pinfunction "1_1") (pintype "passive"))
      (node (ref "PH1") (pin "2") (pinfunction "2_2") (pintype "passive"))
      (node (ref "PIR") (pin "3") (pinfunction "3_3") (pintype "passive"))
      (node (ref "Q2") (pin "E") (pinfunction "E_E") (pintype "passive"))
      (node (ref "Q3") (pin "2") (pinfunction "E_2") (pintype "passive"))
      (node (ref "Q4") (pin "2") (pinfunction "E_2") (pintype "passive"))
      (node (ref "R13") (pin "1") (pinfunction "1_1") (pintype "passive"))
      (node (ref "R19") (pin "1") (pinfunction "1_1") (pintype "passive"))
      (node (ref "R22") (pin "1") (pinfunction "1_1") (pintype "passive"))
      (node (ref "R23") (pin "1") (pinfunction "1_1") (pintype "passive"))
      (node (ref "R31") (pin "1") (pinfunction "1_1") (pintype "passive"))
      (node (ref "R32") (pin "1") (pinfunction "1_1") (pintype "passive"))
      (node (ref "R33") (pin "1") (pinfunction "1_1") (pintype "passive"))
      (node (ref "R36") (pin "1") (pinfunction "1_1") (pintype "passive"))
      (node (ref "R37") (pin "1") (pinfunction "1_1") (pintype "passive"))
      (node (ref "R40") (pin "1") (pinfunction "1_1") (pintype "passive"))
      (node (ref "R41") (pin "1") (pinfunction "1_1") (pintype "passive"))
      (node (ref "R5") (pin "1") (pinfunction "1_1") (pintype "passive"))
      (node (ref "U$1") (pin "P$2") (pinfunction "GND_P$2") (pintype "bidirectional"))
      (node (ref "U$11") (pin "1") (pinfunction "GND_1") (pintype "bidirectional"))
      (node (ref "U$2") (pin "RING") (pinfunction "RING_RING") (pintype "bidirectional"))
      (node (ref "U$2") (pin "RING_SW") (pinfunction "RING_SW_RING_SW") (pintype "bidirectional"))
      (node (ref "U$3") (pin "2") (pinfunction "GND_2") (pintype "bidirectional"))
      (node (ref "U$4") (pin "1") (pinfunction "1_1") (pintype "passive"))
      (node (ref "U$4") (pin "2") (pinfunction "2_2") (pintype "passive"))
      (node (ref "U$5") (pin "P$2") (pinfunction "GND_P$2") (pintype "bidirectional"))
      (node (ref "U$6") (pin "2") (pinfunction "VSS_2") (pintype "bidirectional"))
      (node (ref "U$6") (pin "6") (pinfunction "-IN_6") (pintype "bidirectional"))
      (node (ref "U$8") (pin "2") (pinfunction "VSS_2") (pintype "bidirectional"))
      (node (ref "U$8") (pin "6") (pinfunction "-IN_6") (pintype "bidirectional"))
      (node (ref "U1") (pin "1") (pinfunction "GND_1") (pintype "power_in"))
      (node (ref "U1") (pin "10") (pinfunction "GND_10") (pintype "power_in"))
      (node (ref "U1") (pin "6") (pinfunction "RESET_6") (pintype "input"))
      (node (ref "U1") (pin "8") (pinfunction "GND_8") (pintype "power_in"))
      (node (ref "U2") (pin "11") (pinfunction "GND_11") (pintype "bidirectional"))
      (node (ref "U3") (pin "1") (pinfunction "GND_1") (pintype "power_in"))
      (node (ref "U3") (pin "15") (pinfunction "GND_15") (pintype "power_in"))
      (node (ref "U3") (pin "8") (pinfunction "GND_8") (pintype "power_in"))
      (node (ref "U4") (pin "3") (pinfunction "VSS_3") (pintype "bidirectional"))
      (node (ref "UEXT") (pin "2") (pinfunction "2_2") (pintype "passive"))
      (node (ref "X1") (pin "GND@1") (pinfunction "GND4_GND@1") (pintype "power_in"))
      (node (ref "X1") (pin "GND@2") (pinfunction "GND3_GND@2") (pintype "power_in"))
      (node (ref "X1") (pin "GND@3") (pinfunction "GND2_GND@3") (pintype "power_in"))
      (node (ref "X1") (pin "GND@4") (pinfunction "GND1_GND@4") (pintype "power_in"))
      (node (ref "X2") (pin "2") (pinfunction "KL_2") (pintype "passive"))
    )
    (net (code "17") (name "H_LED") (class "Default")
      (node (ref "CON1") (pin "4") (pinfunction "4_4") (pintype "passive"))
      (node (ref "R18") (pin "2") (pinfunction "2_2") (pintype "passive"))
    )
    (net (code "18") (name "IRQ") (class "Default")
      (node (ref "NRF24L01") (pin "8") (pinfunction "8_8") (pintype "passive"))
    )
    (net (code "19") (name "LORA_CS") (class "Default")
      (node (ref "CON1") (pin "22") (pinfunction "22_22") (pintype "passive"))
      (node (ref "U1") (pin "5") (pinfunction "NSS_5") (pintype "input"))
    )
    (net (code "20") (name "MIC") (class "Default")
      (node (ref "C9") (pin "1") (pinfunction "1_1") (pintype "passive"))
      (node (ref "CON2") (pin "12") (pinfunction "12_12") (pintype "passive"))
      (node (ref "R29") (pin "1") (pinfunction "1_1") (pintype "passive"))
      (node (ref "R6") (pin "1") (pinfunction "1_1") (pintype "passive"))
      (node (ref "U$3") (pin "4") (pinfunction "OUT_4") (pintype "bidirectional"))
    )
    (net (code "21") (name "MISO") (class "Default")
      (node (ref "NRF24L01") (pin "7") (pinfunction "7_7") (pintype "passive"))
      (node (ref "U1") (pin "2") (pinfunction "MISO_2") (pintype "bidirectional"))
      (node (ref "UEXT") (pin "7") (pinfunction "7_7") (pintype "passive"))
    )
    (net (code "22") (name "MOSI") (class "Default")
      (node (ref "NRF24L01") (pin "6") (pinfunction "6_6") (pintype "passive"))
      (node (ref "U1") (pin "3") (pinfunction "MOSI_3") (pintype "input"))
      (node (ref "UEXT") (pin "8") (pinfunction "8_8") (pintype "passive"))
    )
    (net (code "23") (name "NETCHECKUP") (class "Default")
      (node (ref "CON1") (pin "7") (pinfunction "7_7") (pintype "passive"))
    )
    (net (code "24") (name "NETSTAT") (class "Default")
      (node (ref "CON1") (pin "11") (pinfunction "11_11") (pintype "passive"))
      (node (ref "JP1") (pin "12") (pinfunction "12_12") (pintype "passive"))
    )
    (net (code "25") (name "NRF_CS") (class "Default")
      (node (ref "CON1") (pin "21") (pinfunction "21_21") (pintype "passive"))
      (node (ref "NRF24L01") (pin "3") (pinfunction "3_3") (pintype "passive"))
    )
    (net (code "26") (name "NRF_CSN") (class "Default")
      (node (ref "NRF24L01") (pin "4") (pinfunction "4_4") (pintype "passive"))
    )
    (net (code "27") (name "Net-(AVIA-S)") (class "Default")
      (node (ref "AVI") (pin "1") (pinfunction "S_1") (pintype "passive"))
      (node (ref "D1") (pin "3") (pinfunction "C1A2_3") (pintype "passive"))
      (node (ref "R1") (pin "2") (pinfunction "2_2") (pintype "passive"))
    )
    (net (code "28") (name "Net-(C7-Pad1)") (class "Default")
      (node (ref "C7") (pin "1") (pinfunction "1_1") (pintype "passive"))
      (node (ref "R14") (pin "2") (pinfunction "2_2") (pintype "passive"))
      (node (ref "R15") (pin "1") (pinfunction "1_1") (pintype "passive"))
    )
    (net (code "29") (name "Net-(C8-Pad1)") (class "Default")
      (node (ref "C8") (pin "1") (pinfunction "1_1") (pintype "passive"))
      (node (ref "R27") (pin "1") (pinfunction "1_1") (pintype "passive"))
    )
    (net (code "30") (name "Net-(CN1-PadD+)") (class "Default")
      (node (ref "CN1") (pin "D+") (pinfunction "D+_D+") (pintype "bidirectional"))
      (node (ref "R7") (pin "2") (pinfunction "2_2") (pintype "passive"))
    )
    (net (code "31") (name "Net-(CN1-PadD-)") (class "Default")
      (node (ref "CN1") (pin "D-") (pinfunction "D-_D-") (pintype "bidirectional"))
      (node (ref "R10") (pin "2") (pinfunction "2_2") (pintype "passive"))
    )
    (net (code "32") (name "Net-(CON1-Pad24)") (class "Default")
      (node (ref "CON1") (pin "24") (pinfunction "24_24") (pintype "passive"))
      (node (ref "R8") (pin "2") (pinfunction "2_2") (pintype "passive"))
    )
    (net (code "33") (name "Net-(CON1-Pad25)") (class "Default")
      (node (ref "CON1") (pin "25") (pinfunction "25_25") (pintype "passive"))
      (node (ref "R9") (pin "2") (pinfunction "2_2") (pintype "passive"))
    )
    (net (code "34") (name "Net-(CON1-Pad26)") (class "Default")
      (node (ref "CON1") (pin "26") (pinfunction "26_26") (pintype "passive"))
      (node (ref "R20") (pin "1") (pinfunction "1_1") (pintype "passive"))
      (node (ref "U$4") (pin "3") (pinfunction "3_3") (pintype "passive"))
      (node (ref "U$4") (pin "4") (pinfunction "4_4") (pintype "passive"))
    )
    (net (code "35") (name "Net-(FB1-Pad2)") (class "Default")
      (node (ref "FB1") (pin "2") (pinfunction "2_2") (pintype "passive"))
      (node (ref "TOUCH") (pin "4") (pinfunction "4_4") (pintype "passive"))
    )
    (net (code "36") (name "Net-(FB2-Pad2)") (class "Default")
      (node (ref "FB2") (pin "2") (pinfunction "2_2") (pintype "passive"))
      (node (ref "TOUCH") (pin "1") (pinfunction "1_1") (pintype "passive"))
    )
    (net (code "37") (name "Net-(FB3-Pad2)") (class "Default")
      (node (ref "FB3") (pin "2") (pinfunction "2_2") (pintype "passive"))
      (node (ref "JP2") (pin "VBUS") (pinfunction "VBUS_VBUS") (pintype "bidirectional"))
    )
    (net (code "38") (name "Net-(FB4-Pad2)") (class "Default")
      (node (ref "FB4") (pin "2") (pinfunction "2_2") (pintype "passive"))
      (node (ref "JP2") (pin "GND") (pinfunction "GND_GND") (pintype "bidirectional"))
    )
    (net (code "39") (name "Net-(FB5-Pad2)") (class "Default")
      (node (ref "FB5") (pin "2") (pinfunction "2_2") (pintype "passive"))
      (node (ref "JP3") (pin "VBUS") (pinfunction "VBUS_VBUS") (pintype "bidirectional"))
    )
    (net (code "40") (name "Net-(FB6-Pad2)") (class "Default")
      (node (ref "FB6") (pin "2") (pinfunction "2_2") (pintype "passive"))
      (node (ref "JP3") (pin "GND") (pinfunction "GND_GND") (pintype "bidirectional"))
    )
    (net (code "41") (name "Net-(IC1A-+IN)") (class "Default")
      (node (ref "IC1") (pin "3") (pinfunction "+IN_3") (pintype "input"))
      (node (ref "R6") (pin "2") (pinfunction "2_2") (pintype "passive"))
    )
    (net (code "42") (name "Net-(IC1A--IN)") (class "Default")
      (node (ref "D2") (pin "A") (pinfunction "A_A") (pintype "passive"))
      (node (ref "IC1") (pin "1") (pinfunction "OUT_1") (pintype "output"))
      (node (ref "IC1") (pin "2") (pinfunction "-IN_2") (pintype "input"))
    )
    (net (code "43") (name "Net-(IC1B-+IN)") (class "Default")
      (node (ref "IC1") (pin "5") (pinfunction "+IN_5") (pintype "input"))
      (node (ref "U$5") (pin "P$5") (pinfunction "W_P$5") (pintype "bidirectional"))
    )
    (net (code "44") (name "Net-(IC1B--IN)") (class "Default")
      (node (ref "C5") (pin "1") (pinfunction "1_1") (pintype "passive"))
      (node (ref "D2") (pin "C") (pinfunction "C_C") (pintype "passive"))
      (node (ref "IC1") (pin "6") (pinfunction "-IN_6") (pintype "input"))
      (node (ref "R13") (pin "2") (pinfunction "2_2") (pintype "passive"))
    )
    (net (code "45") (name "Net-(IC3-+IN)") (class "Default")
      (node (ref "IC3") (pin "3") (pinfunction "+IN_3") (pintype "input"))
      (node (ref "R23") (pin "2") (pinfunction "2_2") (pintype "passive"))
      (node (ref "R24") (pin "1") (pinfunction "1_1") (pintype "passive"))
      (node (ref "R25") (pin "1") (pinfunction "1_1") (pintype "passive"))
    )
    (net (code "46") (name "Net-(IC3--IN)") (class "Default")
      (node (ref "IC3") (pin "1") (pinfunction "-IN_1") (pintype "input"))
      (node (ref "R21") (pin "2") (pinfunction "2_2") (pintype "passive"))
      (node (ref "R22") (pin "2") (pinfunction "2_2") (pintype "passive"))
    )
    (net (code "47") (name "Net-(IC3-OUT)") (class "Default")
      (node (ref "IC3") (pin "4") (pinfunction "OUT_4") (pintype "output"))
      (node (ref "R25") (pin "2") (pinfunction "2_2") (pintype "passive"))
      (node (ref "R26") (pin "1") (pinfunction "1_1") (pintype "passive"))
    )
    (net (code "48") (name "Net-(IC4A-DM0)") (class "Default")
      (node (ref "C16") (pin "1") (pinfunction "1_1") (pintype "passive"))
      (node (ref "IC4") (pin "2") (pinfunction "DM0_2") (pintype "bidirectional"))
      (node (ref "R10") (pin "1") (pinfunction "1_1") (pintype "passive"))
    )
    (net (code "49") (name "Net-(IC4A-DP0)") (class "Default")
      (node (ref "C17") (pin "1") (pinfunction "1_1") (pintype "passive"))
      (node (ref "IC4") (pin "1") (pinfunction "DP0_1") (pintype "bidirectional"))
      (node (ref "R11") (pin "2") (pinfunction "2_2") (pintype "passive"))
      (node (ref "R7") (pin "1") (pinfunction "1_1") (pintype "passive"))
    )
    (net (code "50") (name "Net-(IC4A-DP0PUR)") (class "Default")
      (node (ref "IC4") (pin "27") (pinfunction "DP0PUR_27") (pintype "output"))
      (node (ref "R11") (pin "1") (pinfunction "1_1") (pintype "passive"))
    )
    (net (code "51") (name "Net-(IC4A-XTAL1)") (class "Default")
      (node (ref "C29") (pin "1") (pinfunction "1_1") (pintype "passive"))
      (node (ref "IC4") (pin "30") (pinfunction "XTAL1_30") (pintype "input"))
      (node (ref "Q1") (pin "2") (pinfunction "2_2") (pintype "passive"))
    )
    (net (code "52") (name "Net-(IC4A-XTAL2)") (class "Default")
      (node (ref "C28") (pin "1") (pinfunction "1_1") (pintype "passive"))
      (node (ref "IC4") (pin "29") (pinfunction "XTAL2_29") (pintype "output"))
      (node (ref "Q1") (pin "1") (pinfunction "1_1") (pintype "passive"))
    )
    (net (code "53") (name "Net-(IC4A-{slash}RESET)") (class "Default")
      (node (ref "C27") (pin "1") (pinfunction "1_1") (pintype "passive"))
      (node (ref "IC4") (pin "4") (pinfunction "/RESET_4") (pintype "input"))
      (node (ref "R42") (pin "2") (pinfunction "2_2") (pintype "passive"))
    )
    (net (code "54") (name "Net-(JP2-PadD+)") (class "Default")
      (node (ref "JP2") (pin "D+") (pinfunction "D+_D+") (pintype "bidirectional"))
      (node (ref "R34") (pin "2") (pinfunction "2_2") (pintype "passive"))
    )
    (net (code "55") (name "Net-(JP2-PadD-)") (class "Default")
      (node (ref "JP2") (pin "D-") (pinfunction "D-_D-") (pintype "bidirectional"))
      (node (ref "R35") (pin "2") (pinfunction "2_2") (pintype "passive"))
    )
    (net (code "56") (name "Net-(JP3-PadD+)") (class "Default")
      (node (ref "JP3") (pin "D+") (pinfunction "D+_D+") (pintype "bidirectional"))
      (node (ref "R38") (pin "2") (pinfunction "2_2") (pintype "passive"))
    )
    (net (code "57") (name "Net-(JP3-PadD-)") (class "Default")
      (node (ref "JP3") (pin "D-") (pinfunction "D-_D-") (pintype "bidirectional"))
      (node (ref "R39") (pin "2") (pinfunction "2_2") (pintype "passive"))
    )
    (net (code "58") (name "Net-(LED1-PadA)") (class "Default")
      (node (ref "LED1") (pin "A") (pinfunction "A_A") (pintype "passive"))
      (node (ref "R8") (pin "1") (pinfunction "1_1") (pintype "passive"))
    )
    (net (code "59") (name "Net-(LED2-PadA)") (class "Default")
      (node (ref "LED2") (pin "A") (pinfunction "A_A") (pintype "passive"))
      (node (ref "R9") (pin "1") (pinfunction "1_1") (pintype "passive"))
    )
    (net (code "60") (name "Net-(MIC-2)") (class "Default")
      (node (ref "C6") (pin "1") (pinfunction "1_1") (pintype "passive"))
      (node (ref "MIC") (pin "+") (pinfunction "2_+") (pintype "passive"))
      (node (ref "R14") (pin "1") (pinfunction "1_1") (pintype "passive"))
      (node (ref "R5") (pin "2") (pinfunction "2_2") (pintype "passive"))
    )
    (net (code "61") (name "Net-(PAD1-P)") (class "Default")
      (node (ref "PAD1") (pin "1") (pinfunction "P_1") (pintype "passive"))
      (node (ref "R12") (pin "1") (pinfunction "1_1") (pintype "passive"))
    )
    (net (code "62") (name "Net-(PAD2-P)") (class "Default")
      (node (ref "PAD2") (pin "1") (pinfunction "P_1") (pintype "passive"))
      (node (ref "Q2") (pin "C") (pinfunction "C_C") (pintype "passive"))
    )
    (net (code "63") (name "Net-(Q3-B)") (class "Default")
      (node (ref "Q3") (pin "1") (pinfunction "B_1") (pintype "passive"))
      (node (ref "R26") (pin "2") (pinfunction "2_2") (pintype "passive"))
    )
    (net (code "64") (name "Net-(Q4-B)") (class "Default")
      (node (ref "Q4") (pin "1") (pinfunction "B_1") (pintype "passive"))
      (node (ref "R17") (pin "1") (pinfunction "1_1") (pintype "passive"))
      (node (ref "R18") (pin "1") (pinfunction "1_1") (pintype "passive"))
      (node (ref "R19") (pin "2") (pinfunction "2_2") (pintype "passive"))
    )
    (net (code "65") (name "Net-(R28-Pad2)") (class "Default")
      (node (ref "R28") (pin "2") (pinfunction "2_2") (pintype "passive"))
      (node (ref "TOUCH") (pin "2") (pinfunction "2_2") (pintype "passive"))
    )
    (net (code "66") (name "Net-(R30-Pad2)") (class "Default")
      (node (ref "R30") (pin "2") (pinfunction "2_2") (pintype "passive"))
      (node (ref "TOUCH") (pin "3") (pinfunction "3_3") (pintype "passive"))
    )
    (net (code "67") (name "Net-(U$1-W)") (class "Default")
      (node (ref "U$1") (pin "P$5") (pinfunction "W_P$5") (pintype "bidirectional"))
      (node (ref "U3") (pin "5") (pinfunction "GAIN_5") (pintype "passive"))
    )
    (net (code "68") (name "Net-(U$3-IN+)") (class "Default")
      (node (ref "C6") (pin "2") (pinfunction "2_2") (pintype "passive"))
      (node (ref "U$3") (pin "1") (pinfunction "IN+_1") (pintype "bidirectional"))
    )
    (net (code "69") (name "Net-(U$3-IN-)") (class "Default")
      (node (ref "C9") (pin "2") (pinfunction "2_2") (pintype "passive"))
      (node (ref "R27") (pin "2") (pinfunction "2_2") (pintype "passive"))
      (node (ref "R29") (pin "2") (pinfunction "2_2") (pintype "passive"))
      (node (ref "U$3") (pin "3") (pinfunction "IN-_3") (pintype "bidirectional"))
    )
    (net (code "70") (name "Net-(U$11-DQ)") (class "Default")
      (node (ref "CON2") (pin "21") (pinfunction "21_21") (pintype "passive"))
      (node (ref "R43") (pin "1") (pinfunction "1_1") (pintype "passive"))
      (node (ref "U$11") (pin "2") (pinfunction "DQ_2") (pintype "bidirectional"))
    )
    (net (code "71") (name "Net-(U1-ANT)") (class "Default")
      (node (ref "U1") (pin "9") (pinfunction "ANT_9") (pintype "passive"))
      (node (ref "X1") (pin "P") (pinfunction "ANT_P") (pintype "bidirectional"))
    )
    (net (code "72") (name "Net-(U1-DIO2)") (class "Default")
      (node (ref "LORA-GPIO") (pin "2") (pinfunction "2_2") (pintype "passive"))
      (node (ref "U1") (pin "16") (pinfunction "DIO2_16") (pintype "bidirectional"))
    )
    (net (code "73") (name "Net-(U1-DIO3)") (class "Default")
      (node (ref "LORA-GPIO") (pin "3") (pinfunction "3_3") (pintype "passive"))
      (node (ref "U1") (pin "11") (pinfunction "DIO3_11") (pintype "bidirectional"))
    )
    (net (code "74") (name "Net-(U1-DIO4)") (class "Default")
      (node (ref "LORA-GPIO") (pin "4") (pinfunction "4_4") (pintype "passive"))
      (node (ref "U1") (pin "12") (pinfunction "DIO4_12") (pintype "bidirectional"))
    )
    (net (code "75") (name "Net-(U1-DIO5)") (class "Default")
      (node (ref "LORA-GPIO") (pin "5") (pinfunction "5_5") (pintype "passive"))
      (node (ref "U1") (pin "7") (pinfunction "DIO5_7") (pintype "bidirectional"))
    )
    (net (code "76") (name "Net-(U2-A5)") (class "Default")
      (node (ref "CON2") (pin "27") (pinfunction "27_27") (pintype "passive"))
      (node (ref "U2") (pin "6") (pinfunction "A5_6") (pintype "bidirectional"))
    )
    (net (code "77") (name "Net-(U2-A6)") (class "Default")
      (node (ref "CON2") (pin "28") (pinfunction "28_28") (pintype "passive"))
      (node (ref "U2") (pin "7") (pinfunction "A6_7") (pintype "bidirectional"))
    )
    (net (code "78") (name "Net-(U2-A7)") (class "Default")
      (node (ref "CON2") (pin "29") (pinfunction "29_29") (pintype "passive"))
      (node (ref "U2") (pin "8") (pinfunction "A7_8") (pintype "bidirectional"))
    )
    (net (code "79") (name "Net-(U2-A8)") (class "Default")
      (node (ref "CON2") (pin "30") (pinfunction "30_30") (pintype "passive"))
      (node (ref "U2") (pin "9") (pinfunction "A8_9") (pintype "bidirectional"))
    )
    (net (code "80") (name "Net-(U2-B5)") (class "Default")
      (node (ref "GPIO") (pin "2") (pinfunction "2_2") (pintype "passive"))
      (node (ref "U2") (pin "15") (pinfunction "B5_15") (pintype "bidirectional"))
    )
    (net (code "81") (name "Net-(U2-B6)") (class "Default")
      (node (ref "GPIO") (pin "3") (pinfunction "3_3") (pintype "passive"))
      (node (ref "U2") (pin "14") (pinfunction "B6_14") (pintype "bidirectional"))
    )
    (net (code "82") (name "Net-(U2-B7)") (class "Default")
      (node (ref "GPIO") (pin "4") (pinfunction "4_4") (pintype "passive"))
      (node (ref "U2") (pin "13") (pinfunction "B7_13") (pintype "bidirectional"))
    )
    (net (code "83") (name "Net-(U2-B8)") (class "Default")
      (node (ref "GPIO") (pin "5") (pinfunction "5_5") (pintype "passive"))
      (node (ref "U2") (pin "12") (pinfunction "B8_12") (pintype "bidirectional"))
    )
    (net (code "84") (name "Net-(U3-INL+)") (class "Default")
      (node (ref "C1") (pin "1") (pinfunction "1_1") (pintype "passive"))
      (node (ref "U3") (pin "3") (pinfunction "INL+_3") (pintype "bidirectional"))
    )
    (net (code "85") (name "Net-(U3-INL-)") (class "Default")
      (node (ref "C3") (pin "1") (pinfunction "1_1") (pintype "passive"))
      (node (ref "U3") (pin "4") (pinfunction "INL-_4") (pintype "bidirectional"))
    )
    (net (code "86") (name "Net-(U3-INR+)") (class "Default")
      (node (ref "C2") (pin "1") (pinfunction "1_1") (pintype "passive"))
      (node (ref "U3") (pin "7") (pinfunction "INR+_7") (pintype "bidirectional"))
    )
    (net (code "87") (name "Net-(U3-INR-)") (class "Default")
      (node (ref "C4") (pin "1") (pinfunction "1_1") (pintype "passive"))
      (node (ref "U3") (pin "6") (pinfunction "INR-_6") (pintype "bidirectional"))
    )
    (net (code "88") (name "Net-(U3-OUTL+)") (class "Default")
      (node (ref "AUDIO") (pin "1") (pinfunction "1_1") (pintype "passive"))
      (node (ref "U3") (pin "13") (pinfunction "OUTL+_13") (pintype "bidirectional"))
    )
    (net (code "89") (name "Net-(U3-OUTL-)") (class "Default")
      (node (ref "AUDIO") (pin "2") (pinfunction "2_2") (pintype "passive"))
      (node (ref "U3") (pin "14") (pinfunction "OUTL-_14") (pintype "bidirectional"))
    )
    (net (code "90") (name "Net-(U3-OUTR+)") (class "Default")
      (node (ref "AUDIO") (pin "3") (pinfunction "3_3") (pintype "passive"))
      (node (ref "U3") (pin "10") (pinfunction "OUTR+_10") (pintype "bidirectional"))
    )
    (net (code "91") (name "Net-(U3-OUTR-)") (class "Default")
      (node (ref "AUDIO") (pin "4") (pinfunction "4_4") (pintype "passive"))
      (node (ref "U3") (pin "9") (pinfunction "OUTR-_9") (pintype "bidirectional"))
    )
    (net (code "92") (name "Net-(U4-AIN0)") (class "Default")
      (node (ref "A_GPIO") (pin "5") (pinfunction "5_5") (pintype "passive"))
      (node (ref "U4") (pin "4") (pinfunction "AIN0_4") (pintype "bidirectional"))
    )
    (net (code "93") (name "Net-(U4-AIN1)") (class "Default")
      (node (ref "A_GPIO") (pin "4") (pinfunction "4_4") (pintype "passive"))
      (node (ref "U4") (pin "5") (pinfunction "AIN1_5") (pintype "bidirectional"))
    )
    (net (code "94") (name "Net-(U4-AIN2)") (class "Default")
      (node (ref "A_GPIO") (pin "3") (pinfunction "3_3") (pintype "passive"))
      (node (ref "SJ2") (pin "2") (pinfunction "2_2") (pintype "passive"))
      (node (ref "U4") (pin "6") (pinfunction "AIN2_6") (pintype "bidirectional"))
    )
    (net (code "95") (name "Net-(U4-AIN3)") (class "Default")
      (node (ref "A_GPIO") (pin "2") (pinfunction "2_2") (pintype "passive"))
      (node (ref "SJ1") (pin "2") (pinfunction "2_2") (pintype "passive"))
      (node (ref "U4") (pin "7") (pinfunction "AIN3_7") (pintype "bidirectional"))
    )
    (net (code "96") (name "PEAK") (class "Default")
      (node (ref "CON1") (pin "13") (pinfunction "13_13") (pintype "passive"))
      (node (ref "IC1") (pin "7") (pinfunction "OUT_7") (pintype "output"))
      (node (ref "TP2") (pin "TP") (pinfunction "TP_TP") (pintype "input"))
    )
    (net (code "97") (name "PHOTO") (class "Default")
      (node (ref "PH1") (pin "1") (pinfunction "1_1") (pintype "passive"))
      (node (ref "R4") (pin "1") (pinfunction "1_1") (pintype "passive"))
      (node (ref "SJ2") (pin "1") (pinfunction "1_1") (pintype "passive"))
      (node (ref "U$6") (pin "1") (pinfunction "+IN_1") (pintype "bidirectional"))
    )
    (net (code "98") (name "PIR") (class "Default")
      (node (ref "CON1") (pin "23") (pinfunction "23_23") (pintype "passive"))
      (node (ref "PIR") (pin "1") (pinfunction "1_1") (pintype "passive"))
    )
    (net (code "99") (name "PWRKEY") (class "Default")
      (node (ref "CON1") (pin "9") (pinfunction "9_9") (pintype "passive"))
      (node (ref "JP1") (pin "9") (pinfunction "9_9") (pintype "passive"))
    )
    (net (code "100") (name "PWRSTAT") (class "Default")
      (node (ref "CON1") (pin "10") (pinfunction "10_10") (pintype "passive"))
      (node (ref "JP1") (pin "11") (pinfunction "11_11") (pintype "passive"))
    )
    (net (code "101") (name "Q18") (class "Default")
      (node (ref "Q2") (pin "B") (pinfunction "B_B") (pintype "passive"))
      (node (ref "Q3") (pin "3") (pinfunction "C_3") (pintype "passive"))
      (node (ref "Q4") (pin "3") (pinfunction "C_3") (pintype "passive"))
      (node (ref "R16") (pin "1") (pinfunction "1_1") (pintype "passive"))
    )
    (net (code "102") (name "RI") (class "Default")
      (node (ref "CON2") (pin "26") (pinfunction "26_26") (pintype "passive"))
      (node (ref "JP1") (pin "10") (pinfunction "10_10") (pintype "passive"))
    )
    (net (code "103") (name "RX") (class "Default")
      (node (ref "JP1") (pin "7") (pinfunction "7_7") (pintype "passive"))
      (node (ref "UEXT") (pin "4") (pinfunction "4_4") (pintype "passive"))
    )
    (net (code "104") (name "SCK") (class "Default")
      (node (ref "NRF24L01") (pin "5") (pinfunction "5_5") (pintype "passive"))
      (node (ref "U1") (pin "4") (pinfunction "SCK_4") (pintype "input"))
      (node (ref "UEXT") (pin "9") (pinfunction "9_9") (pintype "passive"))
    )
    (net (code "105") (name "SCL") (class "Default")
      (node (ref "CON1") (pin "30") (pinfunction "30_30") (pintype "passive"))
      (node (ref "U$1") (pin "P$3") (pinfunction "SCL_P$3") (pintype "bidirectional"))
      (node (ref "U$5") (pin "P$3") (pinfunction "SCL_P$3") (pintype "bidirectional"))
      (node (ref "U$6") (pin "3") (pinfunction "SCL_3") (pintype "bidirectional"))
      (node (ref "U$8") (pin "3") (pinfunction "SCL_3") (pintype "bidirectional"))
      (node (ref "U4") (pin "10") (pinfunction "SCL_10") (pintype "bidirectional"))
      (node (ref "UEXT") (pin "5") (pinfunction "5_5") (pintype "passive"))
    )
    (net (code "106") (name "SDA") (class "Default")
      (node (ref "CON1") (pin "29") (pinfunction "29_29") (pintype "passive"))
      (node (ref "U$1") (pin "P$4") (pinfunction "SDA_P$4") (pintype "bidirectional"))
      (node (ref "U$5") (pin "P$4") (pinfunction "SDA_P$4") (pintype "bidirectional"))
      (node (ref "U$6") (pin "4") (pinfunction "SDL_4") (pintype "bidirectional"))
      (node (ref "U$8") (pin "4") (pinfunction "SDL_4") (pintype "bidirectional"))
      (node (ref "U4") (pin "9") (pinfunction "SDA_9") (pintype "bidirectional"))
      (node (ref "UEXT") (pin "6") (pinfunction "6_6") (pintype "passive"))
    )
    (net (code "107") (name "TX") (class "Default")
      (node (ref "JP1") (pin "6") (pinfunction "6_6") (pintype "passive"))
      (node (ref "UEXT") (pin "3") (pinfunction "3_3") (pintype "passive"))
    )
    (net (code "108") (name "VBAT") (class "Default")
      (node (ref "BAT") (pin "1") (pinfunction "2_1") (pintype "passive"))
      (node (ref "CON1") (pin "1") (pinfunction "1_1") (pintype "passive"))
      (node (ref "SJ1") (pin "1") (pinfunction "1_1") (pintype "passive"))
      (node (ref "U$8") (pin "1") (pinfunction "+IN_1") (pintype "bidirectional"))
    )
    (net (code "109") (name "VDAC") (class "Default")
      (node (ref "CON2") (pin "6") (pinfunction "6_6") (pintype "passive"))
      (node (ref "R1") (pin "1") (pinfunction "1_1") (pintype "passive"))
    )
    (net (code "110") (name "unconnected-(CN1-PadID)") (class "Default")
      (node (ref "CN1") (pin "ID") (pinfunction "ID_ID") (pintype "bidirectional"))
    )
    (net (code "111") (name "unconnected-(CON1-Pad5)") (class "Default")
      (node (ref "CON1") (pin "5") (pinfunction "5_5") (pintype "passive"))
    )
    (net (code "112") (name "unconnected-(CON1-Pad6)") (class "Default")
      (node (ref "CON1") (pin "6") (pinfunction "6_6") (pintype "passive"))
    )
    (net (code "113") (name "unconnected-(CON1-Pad12)") (class "Default")
      (node (ref "CON1") (pin "12") (pinfunction "12_12") (pintype "passive"))
    )
    (net (code "114") (name "unconnected-(CON1-Pad27)") (class "Default")
      (node (ref "CON1") (pin "27") (pinfunction "27_27") (pintype "passive"))
    )
    (net (code "115") (name "unconnected-(CON1-Pad28)") (class "Default")
      (node (ref "CON1") (pin "28") (pinfunction "28_28") (pintype "passive"))
    )
    (net (code "116") (name "unconnected-(CON2-Pad4)") (class "Default")
      (node (ref "CON2") (pin "4") (pinfunction "4_4") (pintype "passive"))
    )
    (net (code "117") (name "unconnected-(CON2-Pad5)") (class "Default")
      (node (ref "CON2") (pin "5") (pinfunction "5_5") (pintype "passive"))
    )
    (net (code "118") (name "unconnected-(CON2-Pad7)") (class "Default")
      (node (ref "CON2") (pin "7") (pinfunction "7_7") (pintype "passive"))
    )
    (net (code "119") (name "unconnected-(CON2-Pad8)") (class "Default")
      (node (ref "CON2") (pin "8") (pinfunction "8_8") (pintype "passive"))
    )
    (net (code "120") (name "unconnected-(CON2-Pad13)") (class "Default")
      (node (ref "CON2") (pin "13") (pinfunction "13_13") (pintype "passive"))
    )
    (net (code "121") (name "unconnected-(CON2-Pad14)") (class "Default")
      (node (ref "CON2") (pin "14") (pinfunction "14_14") (pintype "passive"))
    )
    (net (code "122") (name "unconnected-(CON2-Pad22)") (class "Default")
      (node (ref "CON2") (pin "22") (pinfunction "22_22") (pintype "passive"))
    )
    (net (code "123") (name "unconnected-(CON2-Pad23)") (class "Default")
      (node (ref "CON2") (pin "23") (pinfunction "23_23") (pintype "passive"))
    )
    (net (code "124") (name "unconnected-(CON2-Pad24)") (class "Default")
      (node (ref "CON2") (pin "24") (pinfunction "24_24") (pintype "passive"))
    )
    (net (code "125") (name "unconnected-(CON2-Pad25)") (class "Default")
      (node (ref "CON2") (pin "25") (pinfunction "25_25") (pintype "passive"))
    )
    (net (code "126") (name "unconnected-(IC4A-EECLK-Pad5)") (class "Default")
      (node (ref "IC4") (pin "5") (pinfunction "EECLK_5") (pintype "output"))
    )
    (net (code "127") (name "unconnected-(IC4A-{slash}OVRCUR1-Pad10)") (class "Default")
      (node (ref "IC4") (pin "10") (pinfunction "/OVRCUR1_10") (pintype "input"))
    )
    (net (code "128") (name "unconnected-(IC4A-{slash}OVRCUR2-Pad14)") (class "Default")
      (node (ref "IC4") (pin "14") (pinfunction "/OVRCUR2_14") (pintype "input"))
    )
    (net (code "129") (name "unconnected-(IC4A-{slash}OVRCUR3-Pad18)") (class "Default")
      (node (ref "IC4") (pin "18") (pinfunction "/OVRCUR3_18") (pintype "input"))
    )
    (net (code "130") (name "unconnected-(IC4A-{slash}PWRON1-Pad9)") (class "Default")
      (node (ref "IC4") (pin "9") (pinfunction "/PWRON1_9") (pintype "output"))
    )
    (net (code "131") (name "unconnected-(IC4A-{slash}PWRON2-Pad13)") (class "Default")
      (node (ref "IC4") (pin "13") (pinfunction "/PWRON2_13") (pintype "output"))
    )
    (net (code "132") (name "unconnected-(IC4A-{slash}PWRON3-Pad17)") (class "Default")
      (node (ref "IC4") (pin "17") (pinfunction "/PWRON3_17") (pintype "output"))
    )
    (net (code "133") (name "unconnected-(JP1-Pad2)") (class "Default")
      (node (ref "JP1") (pin "2") (pinfunction "2_2") (pintype "passive"))
    )
    (net (code "134") (name "unconnected-(JP1-Pad5)") (class "Default")
      (node (ref "JP1") (pin "5") (pinfunction "5_5") (pintype "passive"))
    )
    (net (code "135") (name "unconnected-(JP1-Pad8)") (class "Default")
      (node (ref "JP1") (pin "8") (pinfunction "8_8") (pintype "passive"))
    )
    (net (code "136") (name "unconnected-(JP1-Pad13)") (class "Default")
      (node (ref "JP1") (pin "13") (pinfunction "13_13") (pintype "passive"))
    )
    (net (code "137") (name "unconnected-(JP1-Pad14)") (class "Default")
      (node (ref "JP1") (pin "14") (pinfunction "14_14") (pintype "passive"))
    )
    (net (code "138") (name "unconnected-(U1-DIO0-Pad14)") (class "Default")
      (node (ref "U1") (pin "14") (pinfunction "DIO0_14") (pintype "bidirectional"))
    )
    (net (code "139") (name "unconnected-(U1-DIO1-Pad15)") (class "Default")
      (node (ref "U1") (pin "15") (pinfunction "DIO1_15") (pintype "bidirectional"))
    )
    (net (code "140") (name "unconnected-(U2-A1-Pad1)") (class "Default")
      (node (ref "U2") (pin "1") (pinfunction "A1_1") (pintype "bidirectional"))
    )
    (net (code "141") (name "unconnected-(U2-A2-Pad3)") (class "Default")
      (node (ref "U2") (pin "3") (pinfunction "A2_3") (pintype "bidirectional"))
    )
    (net (code "142") (name "unconnected-(U2-A3-Pad4)") (class "Default")
      (node (ref "U2") (pin "4") (pinfunction "A3_4") (pintype "bidirectional"))
    )
    (net (code "143") (name "unconnected-(U2-B1-Pad20)") (class "Default")
      (node (ref "U2") (pin "20") (pinfunction "B1_20") (pintype "bidirectional"))
    )
    (net (code "144") (name "unconnected-(U2-B2-Pad18)") (class "Default")
      (node (ref "U2") (pin "18") (pinfunction "B2_18") (pintype "bidirectional"))
    )
    (net (code "145") (name "unconnected-(U2-B3-Pad17)") (class "Default")
      (node (ref "U2") (pin "17") (pinfunction "B3_17") (pintype "bidirectional"))
    )
    (net (code "146") (name "unconnected-(U2-OE-Pad10)") (class "Default")
      (node (ref "U2") (pin "10") (pinfunction "OE_10") (pintype "bidirectional"))
    )
    (net (code "147") (name "unconnected-(U4-ADDR-Pad1)") (class "Default")
      (node (ref "U4") (pin "1") (pinfunction "ADDR_1") (pintype "bidirectional"))
    )
    (net (code "148") (name "unconnected-(U4-ALERT{slash}RDY-Pad2)") (class "Default")
      (node (ref "U4") (pin "2") (pinfunction "ALERT/RDY_2") (pintype "bidirectional"))
    )
  )
)
